# RHR047A_sch3_Processor_5.net
KiCad netlist of a schematic drawn in Altium Designer
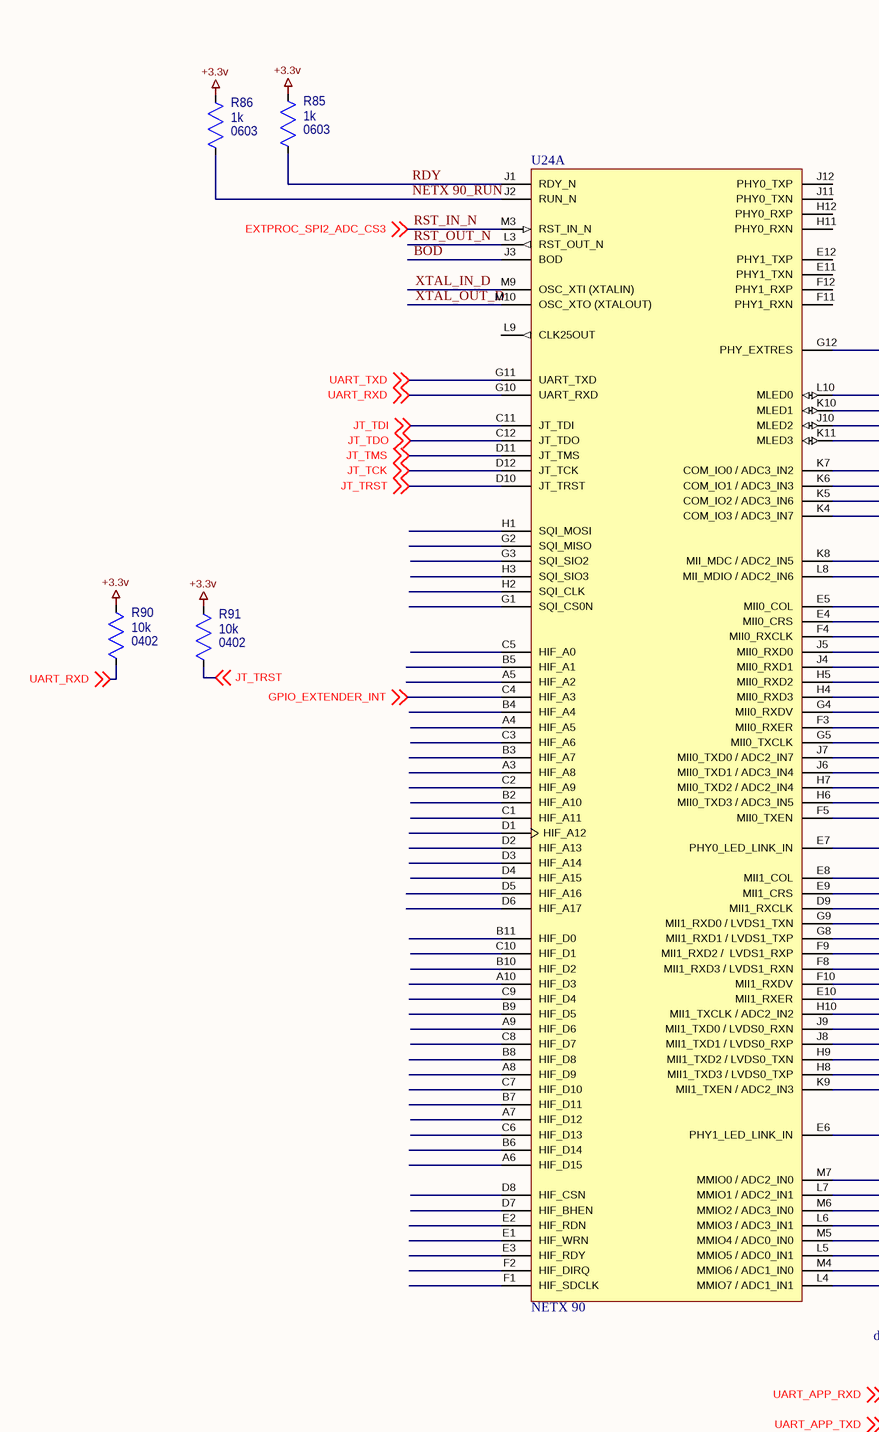
[diagram p0: RHR047A_sch3_Processor_5.SchDoc, left]
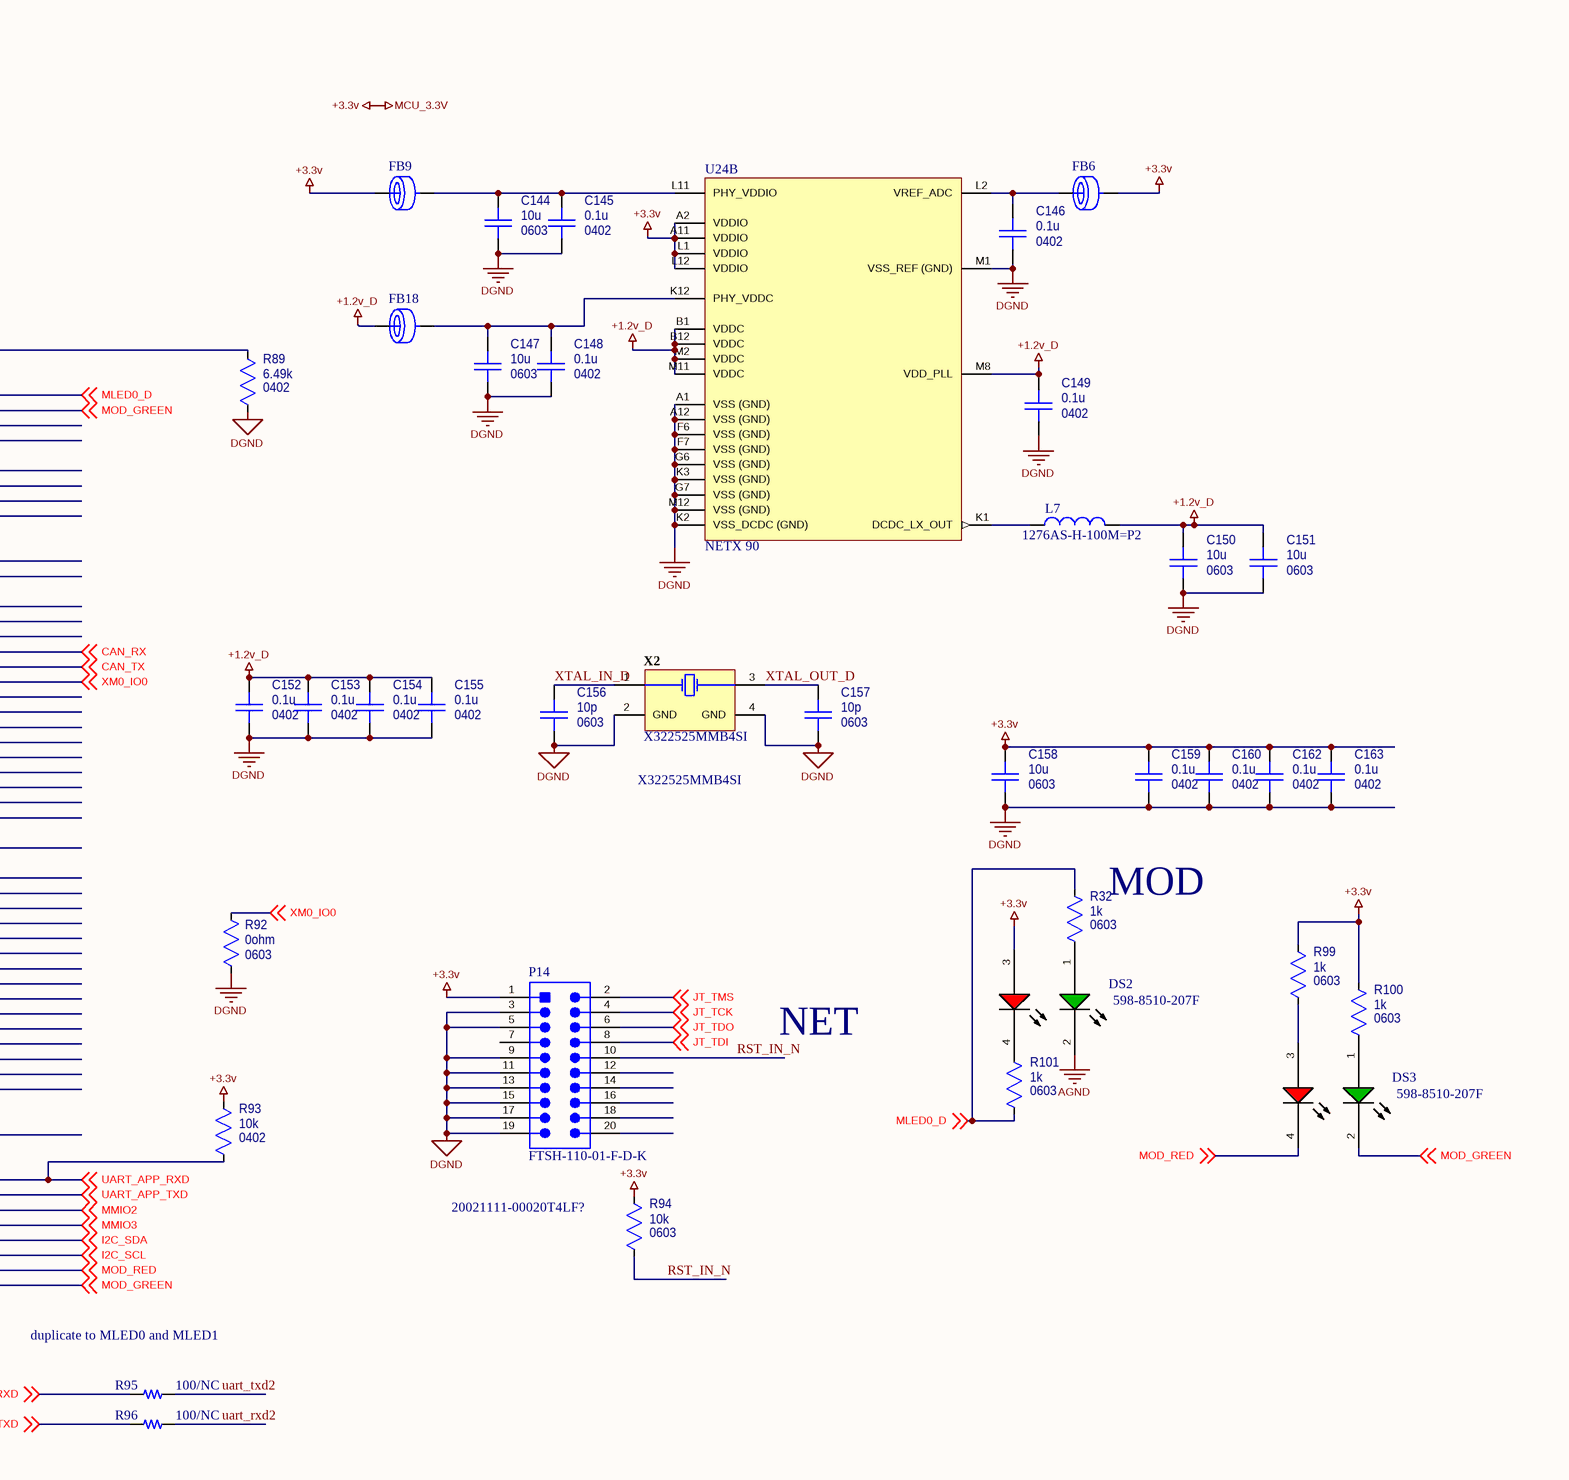
[diagram p1: RHR047A_sch3_Processor_5.SchDoc, right]

(export (version "E")
  (design (tool "Eeschema 10.0.6"))
  (components
    (comp (ref "C144")
      (value "10u")
      (footprint "CAPC1608X092N_0603")
      (description "Capacitor, MLCC")
      (fields
        (field (name "MANUFACTURER") "Murata Electronics")
        (field (name "PARTNUMBER") "GRM188R61A106KE69D")
        (field (name "PACKAGE") "0603")
      )
      (libsource (lib "Karl") (part "Capacitor_0603"))
    )
    (comp (ref "C145")
      (value "0.1u")
      (footprint "CAPC1005X056N_0402")
      (description "Capacitor, MLCC")
      (fields
        (field (name "MANUFACTURER") "Murata Electronics")
        (field (name "PARTNUMBER") "GRM155R71C104KA88J")
        (field (name "PACKAGE") "0402")
      )
      (libsource (lib "Karl") (part "Capacitor_0402"))
    )
    (comp (ref "C146")
      (value "0.1u")
      (footprint "CAPC1005X056N_0402")
      (description "Capacitor, MLCC")
      (fields
        (field (name "MANUFACTURER") "Murata Electronics")
        (field (name "PARTNUMBER") "GRM155R71C104KA88J")
        (field (name "PACKAGE") "0402")
      )
      (libsource (lib "Karl") (part "Capacitor_0402"))
    )
    (comp (ref "C147")
      (value "10u")
      (footprint "CAPC1608X092N_0603")
      (description "Capacitor, MLCC")
      (fields
        (field (name "MANUFACTURER") "Murata Electronics")
        (field (name "PARTNUMBER") "GRM188R61A106KE69D")
        (field (name "PACKAGE") "0603")
      )
      (libsource (lib "Karl") (part "Capacitor_0603"))
    )
    (comp (ref "C148")
      (value "0.1u")
      (footprint "CAPC1005X056N_0402")
      (description "Capacitor, MLCC")
      (fields
        (field (name "MANUFACTURER") "Murata Electronics")
        (field (name "PARTNUMBER") "GRM155R71C104KA88J")
        (field (name "PACKAGE") "0402")
      )
      (libsource (lib "Karl") (part "Capacitor_0402"))
    )
    (comp (ref "C149")
      (value "0.1u")
      (footprint "CAPC1005X056N_0402")
      (description "Capacitor, MLCC")
      (fields
        (field (name "MANUFACTURER") "Murata Electronics")
        (field (name "PARTNUMBER") "GRM155R71C104KA88J")
        (field (name "PACKAGE") "0402")
      )
      (libsource (lib "Karl") (part "Capacitor_0402"))
    )
    (comp (ref "C150")
      (value "10u")
      (footprint "CAPC1608X092N_0603")
      (description "Capacitor, MLCC")
      (fields
        (field (name "MANUFACTURER") "Murata Electronics")
        (field (name "PARTNUMBER") "GRM188R61A106KE69D")
        (field (name "PACKAGE") "0603")
      )
      (libsource (lib "Karl") (part "Capacitor_0603"))
    )
    (comp (ref "C151")
      (value "10u")
      (footprint "CAPC1608X092N_0603")
      (description "Capacitor, MLCC")
      (fields
        (field (name "MANUFACTURER") "Murata Electronics")
        (field (name "PARTNUMBER") "GRM188R61A106KE69D")
        (field (name "PACKAGE") "0603")
      )
      (libsource (lib "Karl") (part "Capacitor_0603"))
    )
    (comp (ref "C152")
      (value "0.1u")
      (footprint "CAPC1005X056N_0402")
      (description "Capacitor, MLCC")
      (fields
        (field (name "MANUFACTURER") "Murata Electronics")
        (field (name "PARTNUMBER") "GRM155R71C104KA88J")
        (field (name "PACKAGE") "0402")
      )
      (libsource (lib "Karl") (part "Capacitor_0402"))
    )
    (comp (ref "C153")
      (value "0.1u")
      (footprint "CAPC1005X056N_0402")
      (description "Capacitor, MLCC")
      (fields
        (field (name "MANUFACTURER") "Murata Electronics")
        (field (name "PARTNUMBER") "GRM155R71C104KA88J")
        (field (name "PACKAGE") "0402")
      )
      (libsource (lib "Karl") (part "Capacitor_0402"))
    )
    (comp (ref "C154")
      (value "0.1u")
      (footprint "CAPC1005X056N_0402")
      (description "Capacitor, MLCC")
      (fields
        (field (name "MANUFACTURER") "Murata Electronics")
        (field (name "PARTNUMBER") "GRM155R71C104KA88J")
        (field (name "PACKAGE") "0402")
      )
      (libsource (lib "Karl") (part "Capacitor_0402"))
    )
    (comp (ref "C155")
      (value "0.1u")
      (footprint "CAPC1005X056N_0402")
      (description "Capacitor, MLCC")
      (fields
        (field (name "MANUFACTURER") "Murata Electronics")
        (field (name "PARTNUMBER") "GRM155R71C104KA88J")
        (field (name "PACKAGE") "0402")
      )
      (libsource (lib "Karl") (part "Capacitor_0402"))
    )
    (comp (ref "C156")
      (value "10p")
      (footprint "CAPC1608X092N_0603")
      (description "Capacitor, MLCC")
      (fields
        (field (name "MANUFACTURER") "Yageo")
        (field (name "PARTNUMBER") "CC0603KRNPO9BN100")
        (field (name "PACKAGE") "0603")
      )
      (libsource (lib "Karl") (part "Capacitor_0603"))
    )
    (comp (ref "C157")
      (value "10p")
      (footprint "CAPC1608X092N_0603")
      (description "Capacitor, MLCC")
      (fields
        (field (name "MANUFACTURER") "Yageo")
        (field (name "PARTNUMBER") "CC0603KRNPO9BN100")
        (field (name "PACKAGE") "0603")
      )
      (libsource (lib "Karl") (part "Capacitor_0603"))
    )
    (comp (ref "C158")
      (value "10u")
      (footprint "CAPC1608X092N_0603")
      (description "Capacitor, MLCC")
      (fields
        (field (name "MANUFACTURER") "Murata Electronics")
        (field (name "PARTNUMBER") "GRM188R61A106KE69D")
        (field (name "PACKAGE") "0603")
      )
      (libsource (lib "Karl") (part "Capacitor_0603"))
    )
    (comp (ref "C159")
      (value "0.1u")
      (footprint "CAPC1005X056N_0402")
      (description "Capacitor, MLCC")
      (fields
        (field (name "MANUFACTURER") "Murata Electronics")
        (field (name "PARTNUMBER") "GRM155R71C104KA88J")
        (field (name "PACKAGE") "0402")
      )
      (libsource (lib "Karl") (part "Capacitor_0402"))
    )
    (comp (ref "C160")
      (value "0.1u")
      (footprint "CAPC1005X056N_0402")
      (description "Capacitor, MLCC")
      (fields
        (field (name "MANUFACTURER") "Murata Electronics")
        (field (name "PARTNUMBER") "GRM155R71C104KA88J")
        (field (name "PACKAGE") "0402")
      )
      (libsource (lib "Karl") (part "Capacitor_0402"))
    )
    (comp (ref "C162")
      (value "0.1u")
      (footprint "CAPC1005X056N_0402")
      (description "Capacitor, MLCC")
      (fields
        (field (name "MANUFACTURER") "Murata Electronics")
        (field (name "PARTNUMBER") "GRM155R71C104KA88J")
        (field (name "PACKAGE") "0402")
      )
      (libsource (lib "Karl") (part "Capacitor_0402"))
    )
    (comp (ref "C163")
      (value "0.1u")
      (footprint "CAPC1005X056N_0402")
      (description "Capacitor, MLCC")
      (fields
        (field (name "MANUFACTURER") "Murata Electronics")
        (field (name "PARTNUMBER") "GRM155R71C104KA88J")
        (field (name "PACKAGE") "0402")
      )
      (libsource (lib "Karl") (part "Capacitor_0402"))
    )
    (comp (ref "DS2")
      (value "598-8510-207F")
      (footprint "DIAL-1208-4_V")
      (description "Bi-Color LED, 2.2 V, -40 to 100 degC, 4-Pin SMD (1208), RoHS, Tape and Reel")
      (fields (field (name "MANUFACTURER") "Dialight"))
      (libsource (lib "Bogen") (part "598-8510-207F"))
    )
    (comp (ref "DS3")
      (value "598-8510-207F")
      (footprint "DIAL-1208-4_V")
      (description "Bi-Color LED, 2.2 V, -40 to 100 degC, 4-Pin SMD (1208), RoHS, Tape and Reel")
      (fields (field (name "MANUFACTURER") "Dialight"))
      (libsource (lib "Bogen") (part "598-8510-207F"))
    )
    (comp (ref "FB6")
      (value "FBC0603")
      (footprint "FBC0603")
      (description "Ferrite Bead Chip")
      (fields
        (field (name "MANUFACTURER") "Pulse Electronics Network")
        (field (name "PARTNUMBER") "PE-0603PFB121ST")
      )
      (libsource (lib "Karl") (part "FBC0603"))
    )
    (comp (ref "FB9")
      (value "FBC0603")
      (footprint "FBC0603")
      (description "Ferrite Bead Chip")
      (fields
        (field (name "MANUFACTURER") "Pulse Electronics Network")
        (field (name "PARTNUMBER") "PE-0603PFB121ST")
      )
      (libsource (lib "Karl") (part "FBC0603"))
    )
    (comp (ref "FB18")
      (value "FBC0603")
      (footprint "FBC0603")
      (description "Ferrite Bead Chip")
      (fields
        (field (name "MANUFACTURER") "Pulse Electronics Network")
        (field (name "PARTNUMBER") "PE-0603PFB121ST")
      )
      (libsource (lib "Karl") (part "FBC0603"))
    )
    (comp (ref "L7")
      (value "1276AS-H-100M=P2")
      (footprint "MURA-IND1210_V")
      (description "Metal alloy Power Inductor, 10 uH, ±20%, 1210 (3225)")
      (fields (field (name "MANUFACTURER") "Murata"))
      (libsource (lib "Bogen") (part "1276AS-H-100M=P2"))
    )
    (comp (ref "P14")
      (value "FTSH-110-01-F-D-K")
      (footprint "SMTC-FTSH-110-01-F-D-K_V")
      (description "Male Header, Pitch 1.27 mm, 2 x 10 Position, Height 6.25 mm, -55 to 125 degC, RoHS")
      (fields (field (name "MANUFACTURER") "Samtec-Inc."))
      (libsource (lib "Bogen") (part "FTSH-110-01-F-D-K"))
    )
    (comp (ref "R32")
      (value "1k")
      (footprint "RESC1608X055N_0603")
      (description "Resistor, Standard")
      (fields
        (field (name "MANUFACTURER") "Yageo")
        (field (name "PARTNUMBER") "RC0603FR-071KL")
        (field (name "PACKAGE") "0603")
      )
      (libsource (lib "Karl") (part "Resistor_0603"))
    )
    (comp (ref "R85")
      (value "1k")
      (footprint "RESC1608X055N_0603")
      (description "Resistor, Standard")
      (fields
        (field (name "MANUFACTURER") "Yageo")
        (field (name "PARTNUMBER") "RC0603FR-071KL")
        (field (name "PACKAGE") "0603")
      )
      (libsource (lib "Karl") (part "Resistor_0603"))
    )
    (comp (ref "R86")
      (value "1k")
      (footprint "RESC1608X055N_0603")
      (description "Resistor, Standard")
      (fields
        (field (name "MANUFACTURER") "Yageo")
        (field (name "PARTNUMBER") "RC0603FR-071KL")
        (field (name "PACKAGE") "0603")
      )
      (libsource (lib "Karl") (part "Resistor_0603"))
    )
    (comp (ref "R89")
      (value "6.49k")
      (footprint "RESC1005X040N_0402")
      (description "Resistor, Standard")
      (fields
        (field (name "MANUFACTURER") "Yageo")
        (field (name "PARTNUMBER") "RC0402FR-076K49L")
        (field (name "PACKAGE") "0402")
      )
      (libsource (lib "Karl") (part "Resistor_0402"))
    )
    (comp (ref "R90")
      (value "10k")
      (footprint "RESC1005X040N_0402")
      (description "Resistor, Standard")
      (fields
        (field (name "MANUFACTURER") "Panasonic")
        (field (name "PARTNUMBER") "ERJ-2RKF1002X")
        (field (name "PACKAGE") "0402")
      )
      (libsource (lib "Karl") (part "Resistor_0402"))
    )
    (comp (ref "R91")
      (value "10k")
      (footprint "RESC1005X040N_0402")
      (description "Resistor, Standard")
      (fields
        (field (name "MANUFACTURER") "Panasonic")
        (field (name "PARTNUMBER") "ERJ-2RKF1002X")
        (field (name "PACKAGE") "0402")
      )
      (libsource (lib "Karl") (part "Resistor_0402"))
    )
    (comp (ref "R92")
      (value "0ohm")
      (footprint "RESC1608X055N_0603")
      (description "Resistor, Standard")
      (fields
        (field (name "MANUFACTURER") "Yageo")
        (field (name "PARTNUMBER") "RC0603JR-070RL")
        (field (name "PACKAGE") "0603")
      )
      (libsource (lib "Karl") (part "Resistor_0603"))
    )
    (comp (ref "R93")
      (value "10k")
      (footprint "RESC1005X040N_0402")
      (description "Resistor, Standard")
      (fields
        (field (name "MANUFACTURER") "Panasonic")
        (field (name "PARTNUMBER") "ERJ-2RKF1002X")
        (field (name "PACKAGE") "0402")
      )
      (libsource (lib "Karl") (part "Resistor_0402"))
    )
    (comp (ref "R94")
      (value "10k")
      (footprint "RESC1608X055N_0603")
      (description "Resistor, Standard")
      (fields
        (field (name "MANUFACTURER") "Yageo")
        (field (name "PARTNUMBER") "RC0603FR-0710KL")
        (field (name "PACKAGE") "0603")
      )
      (libsource (lib "Karl") (part "Resistor_0603"))
    )
    (comp (ref "R95")
      (value "100/NC")
      (footprint "0603R")
      (description "R")
      (libsource (lib "JRJ_1") (part "R"))
    )
    (comp (ref "R96")
      (value "100/NC")
      (footprint "0603R")
      (description "R")
      (libsource (lib "JRJ_1") (part "R"))
    )
    (comp (ref "R99")
      (value "1k")
      (footprint "RESC1608X055N_0603")
      (description "Resistor, Standard")
      (fields
        (field (name "MANUFACTURER") "Yageo")
        (field (name "PARTNUMBER") "RC0603FR-071KL")
        (field (name "PACKAGE") "0603")
      )
      (libsource (lib "Karl") (part "Resistor_0603"))
    )
    (comp (ref "R100")
      (value "1k")
      (footprint "RESC1608X055N_0603")
      (description "Resistor, Standard")
      (fields
        (field (name "MANUFACTURER") "Yageo")
        (field (name "PARTNUMBER") "RC0603FR-071KL")
        (field (name "PACKAGE") "0603")
      )
      (libsource (lib "Karl") (part "Resistor_0603"))
    )
    (comp (ref "R101")
      (value "1k")
      (footprint "RESC1608X055N_0603")
      (description "Resistor, Standard")
      (fields
        (field (name "MANUFACTURER") "Yageo")
        (field (name "PARTNUMBER") "RC0603FR-071KL")
        (field (name "PACKAGE") "0603")
      )
      (libsource (lib "Karl") (part "Resistor_0603"))
    )
    (comp (ref "U24")
      (value "NETX 90")
      (footprint "HILSCH-LFBGA144_V")
      (libsource (lib "Bogen") (part "NETX 90"))
    )
    (comp (ref "X2")
      (value "X322525MMB4SI")
      (footprint "TXC-7M-4_V")
      (description "Seam Crystal, 7M Series, 3 pF, -40 to 85 degC, 4-Pin SMD, RoHS, Tape and Reel")
      (fields (field (name "MANUFACTURER") "TXC"))
      (libsource (lib "Bogen") (part "7M-25.000MEEQ-T"))
    )
  )
  (nets
    (net (code "1") (name "+1.2v_D") (class "Default")
      (node (ref "C149") (pin "1") (pinfunction "1_1") (pintype "passive"))
      (node (ref "C150") (pin "1") (pinfunction "1_1") (pintype "passive"))
      (node (ref "C151") (pin "1") (pinfunction "1_1") (pintype "passive"))
      (node (ref "C152") (pin "1") (pinfunction "1_1") (pintype "passive"))
      (node (ref "C153") (pin "1") (pinfunction "1_1") (pintype "passive"))
      (node (ref "C154") (pin "1") (pinfunction "1_1") (pintype "passive"))
      (node (ref "C155") (pin "1") (pinfunction "1_1") (pintype "passive"))
      (node (ref "FB18") (pin "1") (pinfunction "1_1") (pintype "passive"))
      (node (ref "L7") (pin "2") (pinfunction "2_2") (pintype "passive"))
      (node (ref "U24") (pin "B1") (pinfunction "VDDC_B1") (pintype "power_in"))
      (node (ref "U24") (pin "B12") (pinfunction "VDDC_B12") (pintype "power_in"))
      (node (ref "U24") (pin "M11") (pinfunction "VDDC_M11") (pintype "power_in"))
      (node (ref "U24") (pin "M2") (pinfunction "VDDC_M2") (pintype "power_in"))
      (node (ref "U24") (pin "M8") (pinfunction "VDD_PLL_M8") (pintype "power_in"))
    )
    (net (code "2") (name "+3.3v") (class "Default")
      (node (ref "C158") (pin "1") (pinfunction "1_1") (pintype "passive"))
      (node (ref "C159") (pin "1") (pinfunction "1_1") (pintype "passive"))
      (node (ref "C160") (pin "1") (pinfunction "1_1") (pintype "passive"))
      (node (ref "C162") (pin "1") (pinfunction "1_1") (pintype "passive"))
      (node (ref "C163") (pin "1") (pinfunction "1_1") (pintype "passive"))
      (node (ref "DS2") (pin "3") (pinfunction "RED-A_3") (pintype "passive"))
      (node (ref "FB6") (pin "2") (pinfunction "2_2") (pintype "passive"))
      (node (ref "FB9") (pin "1") (pinfunction "1_1") (pintype "passive"))
      (node (ref "P14") (pin "1") (pinfunction "1_1") (pintype "passive"))
      (node (ref "R100") (pin "2") (pinfunction "2_2") (pintype "passive"))
      (node (ref "R85") (pin "2") (pinfunction "2_2") (pintype "passive"))
      (node (ref "R86") (pin "2") (pinfunction "2_2") (pintype "passive"))
      (node (ref "R90") (pin "2") (pinfunction "2_2") (pintype "passive"))
      (node (ref "R91") (pin "2") (pinfunction "2_2") (pintype "passive"))
      (node (ref "R93") (pin "2") (pinfunction "2_2") (pintype "passive"))
      (node (ref "R94") (pin "2") (pinfunction "2_2") (pintype "passive"))
      (node (ref "R99") (pin "2") (pinfunction "2_2") (pintype "passive"))
      (node (ref "U24") (pin "A11") (pinfunction "VDDIO_A11") (pintype "power_in"))
      (node (ref "U24") (pin "A2") (pinfunction "VDDIO_A2") (pintype "power_in"))
      (node (ref "U24") (pin "L1") (pinfunction "VDDIO_L1") (pintype "power_in"))
      (node (ref "U24") (pin "L12") (pinfunction "VDDIO_L12") (pintype "power_in"))
    )
    (net (code "3") (name "/BOD") (class "Default")
      (node (ref "U24") (pin "J3") (pinfunction "BOD_J3") (pintype "passive"))
    )
    (net (code "4") (name "/NETX 90_RUN") (class "Default")
      (node (ref "R86") (pin "1") (pinfunction "1_1") (pintype "passive"))
      (node (ref "U24") (pin "J2") (pinfunction "RUN_N_J2") (pintype "passive"))
    )
    (net (code "5") (name "/RDY") (class "Default")
      (node (ref "R85") (pin "1") (pinfunction "1_1") (pintype "passive"))
      (node (ref "U24") (pin "J1") (pinfunction "RDY_N_J1") (pintype "passive"))
    )
    (net (code "6") (name "/RST_OUT_N") (class "Default")
      (node (ref "U24") (pin "L3") (pinfunction "RST_OUT_N_L3") (pintype "output"))
    )
    (net (code "7") (name "/XTAL_IN_D") (class "Default")
      (node (ref "C156") (pin "1") (pinfunction "1_1") (pintype "passive"))
      (node (ref "U24") (pin "M9") (pinfunction "OSC_XTI_(XTALIN)_M9") (pintype "passive"))
      (node (ref "X2") (pin "1") (pinfunction "X1_1") (pintype "passive"))
    )
    (net (code "8") (name "/XTAL_OUT_D") (class "Default")
      (node (ref "C157") (pin "1") (pinfunction "1_1") (pintype "passive"))
      (node (ref "U24") (pin "M10") (pinfunction "OSC_XTO_(XTALOUT)_M10") (pintype "passive"))
      (node (ref "X2") (pin "3") (pinfunction "X2_3") (pintype "passive"))
    )
    (net (code "9") (name "/uart_rxd2") (class "Default") (node (ref "R96") (pin "2") (pintype "passive")))
    (net (code "10") (name "/uart_txd2") (class "Default") (node (ref "R95") (pin "2") (pintype "passive")))
    (net (code "11") (name "AGND") (class "Default")
      (node (ref "DS2") (pin "2") (pinfunction "GREEN-K_2") (pintype "passive"))
    )
    (net (code "12") (name "CAN_RX") (class "Default")
      (node (ref "U24") (pin "J5") (pinfunction "MII0_RXD0_J5") (pintype "passive"))
    )
    (net (code "13") (name "CAN_TX") (class "Default")
      (node (ref "U24") (pin "J4") (pinfunction "MII0_RXD1_J4") (pintype "passive"))
    )
    (net (code "14") (name "DGND") (class "Default")
      (node (ref "C144") (pin "2") (pinfunction "2_2") (pintype "passive"))
      (node (ref "C145") (pin "2") (pinfunction "2_2") (pintype "passive"))
      (node (ref "C146") (pin "2") (pinfunction "2_2") (pintype "passive"))
      (node (ref "C147") (pin "2") (pinfunction "2_2") (pintype "passive"))
      (node (ref "C148") (pin "2") (pinfunction "2_2") (pintype "passive"))
      (node (ref "C149") (pin "2") (pinfunction "2_2") (pintype "passive"))
      (node (ref "C150") (pin "2") (pinfunction "2_2") (pintype "passive"))
      (node (ref "C151") (pin "2") (pinfunction "2_2") (pintype "passive"))
      (node (ref "C152") (pin "2") (pinfunction "2_2") (pintype "passive"))
      (node (ref "C153") (pin "2") (pinfunction "2_2") (pintype "passive"))
      (node (ref "C154") (pin "2") (pinfunction "2_2") (pintype "passive"))
      (node (ref "C155") (pin "2") (pinfunction "2_2") (pintype "passive"))
      (node (ref "C156") (pin "2") (pinfunction "2_2") (pintype "passive"))
      (node (ref "C157") (pin "2") (pinfunction "2_2") (pintype "passive"))
      (node (ref "C158") (pin "2") (pinfunction "2_2") (pintype "passive"))
      (node (ref "C159") (pin "2") (pinfunction "2_2") (pintype "passive"))
      (node (ref "C160") (pin "2") (pinfunction "2_2") (pintype "passive"))
      (node (ref "C162") (pin "2") (pinfunction "2_2") (pintype "passive"))
      (node (ref "C163") (pin "2") (pinfunction "2_2") (pintype "passive"))
      (node (ref "P14") (pin "11") (pinfunction "11_11") (pintype "passive"))
      (node (ref "P14") (pin "13") (pinfunction "13_13") (pintype "passive"))
      (node (ref "P14") (pin "15") (pinfunction "15_15") (pintype "passive"))
      (node (ref "P14") (pin "17") (pinfunction "17_17") (pintype "passive"))
      (node (ref "P14") (pin "19") (pinfunction "19_19") (pintype "passive"))
      (node (ref "P14") (pin "3") (pinfunction "3_3") (pintype "passive"))
      (node (ref "P14") (pin "5") (pinfunction "5_5") (pintype "passive"))
      (node (ref "P14") (pin "9") (pinfunction "9_9") (pintype "passive"))
      (node (ref "R89") (pin "1") (pinfunction "1_1") (pintype "passive"))
      (node (ref "R92") (pin "2") (pinfunction "2_2") (pintype "passive"))
      (node (ref "U24") (pin "A1") (pinfunction "VSS_(GND)_A1") (pintype "power_in"))
      (node (ref "U24") (pin "A12") (pinfunction "VSS_(GND)_A12") (pintype "power_in"))
      (node (ref "U24") (pin "F6") (pinfunction "VSS_(GND)_F6") (pintype "power_in"))
      (node (ref "U24") (pin "F7") (pinfunction "VSS_(GND)_F7") (pintype "power_in"))
      (node (ref "U24") (pin "G6") (pinfunction "VSS_(GND)_G6") (pintype "power_in"))
      (node (ref "U24") (pin "G7") (pinfunction "VSS_(GND)_G7") (pintype "power_in"))
      (node (ref "U24") (pin "K2") (pinfunction "VSS_DCDC_(GND)_K2") (pintype "power_in"))
      (node (ref "U24") (pin "K3") (pinfunction "VSS_(GND)_K3") (pintype "power_in"))
      (node (ref "U24") (pin "M1") (pinfunction "VSS_REF_(GND)_M1") (pintype "power_in"))
      (node (ref "U24") (pin "M12") (pinfunction "VSS_(GND)_M12") (pintype "power_in"))
      (node (ref "X2") (pin "2") (pinfunction "GND_2") (pintype "power_in"))
      (node (ref "X2") (pin "4") (pinfunction "GND_4") (pintype "power_in"))
    )
    (net (code "15") (name "EXTPROC_SPI2_ADC_CS3") (class "Default")
      (node (ref "P14") (pin "10") (pinfunction "10_10") (pintype "passive"))
      (node (ref "R94") (pin "1") (pinfunction "1_1") (pintype "passive"))
      (node (ref "U24") (pin "M3") (pinfunction "RST_IN_N_M3") (pintype "input"))
    )
    (net (code "16") (name "GPIO_EXTENDER_INT") (class "Default")
      (node (ref "U24") (pin "C4") (pinfunction "HIF_A3_C4") (pintype "passive"))
    )
    (net (code "17") (name "I2C_SCL") (class "Default")
      (node (ref "U24") (pin "L5") (pinfunction "MMIO5_/_ADC0_IN1_L5") (pintype "passive"))
    )
    (net (code "18") (name "I2C_SDA") (class "Default")
      (node (ref "U24") (pin "M5") (pinfunction "MMIO4_/_ADC0_IN0_M5") (pintype "passive"))
    )
    (net (code "19") (name "JT_TCK") (class "Default")
      (node (ref "P14") (pin "4") (pinfunction "4_4") (pintype "passive"))
      (node (ref "U24") (pin "D12") (pinfunction "JT_TCK_D12") (pintype "passive"))
    )
    (net (code "20") (name "JT_TDI") (class "Default")
      (node (ref "P14") (pin "8") (pinfunction "8_8") (pintype "passive"))
      (node (ref "U24") (pin "C11") (pinfunction "JT_TDI_C11") (pintype "passive"))
    )
    (net (code "21") (name "JT_TDO") (class "Default")
      (node (ref "P14") (pin "6") (pinfunction "6_6") (pintype "passive"))
      (node (ref "U24") (pin "C12") (pinfunction "JT_TDO_C12") (pintype "passive"))
    )
    (net (code "22") (name "JT_TMS") (class "Default")
      (node (ref "P14") (pin "2") (pinfunction "2_2") (pintype "passive"))
      (node (ref "U24") (pin "D11") (pinfunction "JT_TMS_D11") (pintype "passive"))
    )
    (net (code "23") (name "JT_TRST") (class "Default")
      (node (ref "R91") (pin "1") (pinfunction "1_1") (pintype "passive"))
      (node (ref "U24") (pin "D10") (pinfunction "JT_TRST_D10") (pintype "passive"))
    )
    (net (code "24") (name "MLED0_D") (class "Default")
      (node (ref "R101") (pin "1") (pinfunction "1_1") (pintype "passive"))
      (node (ref "R32") (pin "2") (pinfunction "2_2") (pintype "passive"))
      (node (ref "U24") (pin "L10") (pinfunction "MLED0_L10") (pintype "bidirectional"))
    )
    (net (code "25") (name "MMIO2") (class "Default")
      (node (ref "U24") (pin "M6") (pinfunction "MMIO2_/_ADC3_IN0_M6") (pintype "passive"))
    )
    (net (code "26") (name "MMIO3") (class "Default")
      (node (ref "U24") (pin "L6") (pinfunction "MMIO3_/_ADC3_IN1_L6") (pintype "passive"))
    )
    (net (code "27") (name "MOD_GREEN") (class "Default")
      (node (ref "DS3") (pin "2") (pinfunction "GREEN-K_2") (pintype "passive"))
      (node (ref "U24") (pin "K10") (pinfunction "MLED1_K10") (pintype "bidirectional"))
      (node (ref "U24") (pin "L4") (pinfunction "MMIO7_/_ADC1_IN1_L4") (pintype "passive"))
    )
    (net (code "28") (name "MOD_RED") (class "Default")
      (node (ref "DS3") (pin "4") (pinfunction "RED-K_4") (pintype "passive"))
      (node (ref "U24") (pin "M4") (pinfunction "MMIO6_/_ADC1_IN0_M4") (pintype "passive"))
    )
    (net (code "29") (name "Net-(DS2-GREEN-A)") (class "Default")
      (node (ref "DS2") (pin "1") (pinfunction "GREEN-A_1") (pintype "passive"))
      (node (ref "R32") (pin "1") (pinfunction "1_1") (pintype "passive"))
    )
    (net (code "30") (name "Net-(DS2-RED-K)") (class "Default")
      (node (ref "DS2") (pin "4") (pinfunction "RED-K_4") (pintype "passive"))
      (node (ref "R101") (pin "2") (pinfunction "2_2") (pintype "passive"))
    )
    (net (code "31") (name "Net-(DS3-GREEN-A)") (class "Default")
      (node (ref "DS3") (pin "1") (pinfunction "GREEN-A_1") (pintype "passive"))
      (node (ref "R100") (pin "1") (pinfunction "1_1") (pintype "passive"))
    )
    (net (code "32") (name "Net-(DS3-RED-A)") (class "Default")
      (node (ref "DS3") (pin "3") (pinfunction "RED-A_3") (pintype "passive"))
      (node (ref "R99") (pin "1") (pinfunction "1_1") (pintype "passive"))
    )
    (net (code "33") (name "Net-(U24A-PHY_EXTRES)") (class "Default")
      (node (ref "R89") (pin "2") (pinfunction "2_2") (pintype "passive"))
      (node (ref "U24") (pin "G12") (pinfunction "PHY_EXTRES_G12") (pintype "passive"))
    )
    (net (code "34") (name "Net-(U24B-DCDC_LX_OUT)") (class "Default")
      (node (ref "L7") (pin "1") (pinfunction "1_1") (pintype "passive"))
      (node (ref "U24") (pin "K1") (pinfunction "DCDC_LX_OUT_K1") (pintype "output"))
    )
    (net (code "35") (name "Net-(U24B-PHY_VDDC)") (class "Default")
      (node (ref "C147") (pin "1") (pinfunction "1_1") (pintype "passive"))
      (node (ref "C148") (pin "1") (pinfunction "1_1") (pintype "passive"))
      (node (ref "FB18") (pin "2") (pinfunction "2_2") (pintype "passive"))
      (node (ref "U24") (pin "K12") (pinfunction "PHY_VDDC_K12") (pintype "power_in"))
    )
    (net (code "36") (name "Net-(U24B-PHY_VDDIO)") (class "Default")
      (node (ref "C144") (pin "1") (pinfunction "1_1") (pintype "passive"))
      (node (ref "C145") (pin "1") (pinfunction "1_1") (pintype "passive"))
      (node (ref "FB9") (pin "2") (pinfunction "2_2") (pintype "passive"))
      (node (ref "U24") (pin "L11") (pinfunction "PHY_VDDIO_L11") (pintype "power_in"))
    )
    (net (code "37") (name "Net-(U24B-VREF_ADC)") (class "Default")
      (node (ref "C146") (pin "1") (pinfunction "1_1") (pintype "passive"))
      (node (ref "FB6") (pin "1") (pinfunction "1_1") (pintype "passive"))
      (node (ref "U24") (pin "L2") (pinfunction "VREF_ADC_L2") (pintype "power_in"))
    )
    (net (code "38") (name "UART_APP_RXD") (class "Default")
      (node (ref "R93") (pin "1") (pinfunction "1_1") (pintype "passive"))
      (node (ref "R95") (pin "1") (pintype "passive"))
      (node (ref "U24") (pin "M7") (pinfunction "MMIO0_/_ADC2_IN0_M7") (pintype "passive"))
    )
    (net (code "39") (name "UART_APP_TXD") (class "Default")
      (node (ref "R96") (pin "1") (pintype "passive"))
      (node (ref "U24") (pin "L7") (pinfunction "MMIO1_/_ADC2_IN1_L7") (pintype "passive"))
    )
    (net (code "40") (name "UART_RXD") (class "Default")
      (node (ref "R90") (pin "1") (pinfunction "1_1") (pintype "passive"))
      (node (ref "U24") (pin "G10") (pinfunction "UART_RXD_G10") (pintype "passive"))
    )
    (net (code "41") (name "UART_TXD") (class "Default")
      (node (ref "U24") (pin "G11") (pinfunction "UART_TXD_G11") (pintype "passive"))
    )
    (net (code "42") (name "XM0_IO0") (class "Default")
      (node (ref "R92") (pin "1") (pinfunction "1_1") (pintype "passive"))
      (node (ref "U24") (pin "H5") (pinfunction "MII0_RXD2_H5") (pintype "passive"))
    )
    (net (code "43") (name "unconnected-(P14-Pad7)") (class "Default")
      (node (ref "P14") (pin "7") (pinfunction "7_7") (pintype "passive"))
    )
    (net (code "44") (name "unconnected-(P14-Pad12)") (class "Default")
      (node (ref "P14") (pin "12") (pinfunction "12_12") (pintype "passive"))
    )
    (net (code "45") (name "unconnected-(P14-Pad14)") (class "Default")
      (node (ref "P14") (pin "14") (pinfunction "14_14") (pintype "passive"))
    )
    (net (code "46") (name "unconnected-(P14-Pad16)") (class "Default")
      (node (ref "P14") (pin "16") (pinfunction "16_16") (pintype "passive"))
    )
    (net (code "47") (name "unconnected-(P14-Pad18)") (class "Default")
      (node (ref "P14") (pin "18") (pinfunction "18_18") (pintype "passive"))
    )
    (net (code "48") (name "unconnected-(P14-Pad20)") (class "Default")
      (node (ref "P14") (pin "20") (pinfunction "20_20") (pintype "passive"))
    )
    (net (code "49") (name "unconnected-(U24A-CLK25OUT-PadL9)") (class "Default")
      (node (ref "U24") (pin "L9") (pinfunction "CLK25OUT_L9") (pintype "output"))
    )
    (net (code "50") (name "unconnected-(U24A-COM_IO0_{slash}_ADC3_IN2-PadK7)") (class "Default")
      (node (ref "U24") (pin "K7") (pinfunction "COM_IO0_/_ADC3_IN2_K7") (pintype "passive"))
    )
    (net (code "51") (name "unconnected-(U24A-COM_IO1_{slash}_ADC3_IN3-PadK6)") (class "Default")
      (node (ref "U24") (pin "K6") (pinfunction "COM_IO1_/_ADC3_IN3_K6") (pintype "passive"))
    )
    (net (code "52") (name "unconnected-(U24A-COM_IO2_{slash}_ADC3_IN6-PadK5)") (class "Default")
      (node (ref "U24") (pin "K5") (pinfunction "COM_IO2_/_ADC3_IN6_K5") (pintype "passive"))
    )
    (net (code "53") (name "unconnected-(U24A-COM_IO3_{slash}_ADC3_IN7-PadK4)") (class "Default")
      (node (ref "U24") (pin "K4") (pinfunction "COM_IO3_/_ADC3_IN7_K4") (pintype "passive"))
    )
    (net (code "54") (name "unconnected-(U24A-HIF_A0-PadC5)") (class "Default")
      (node (ref "U24") (pin "C5") (pinfunction "HIF_A0_C5") (pintype "passive"))
    )
    (net (code "55") (name "unconnected-(U24A-HIF_A1-PadB5)") (class "Default")
      (node (ref "U24") (pin "B5") (pinfunction "HIF_A1_B5") (pintype "passive"))
    )
    (net (code "56") (name "unconnected-(U24A-HIF_A2-PadA5)") (class "Default")
      (node (ref "U24") (pin "A5") (pinfunction "HIF_A2_A5") (pintype "passive"))
    )
    (net (code "57") (name "unconnected-(U24A-HIF_A4-PadB4)") (class "Default")
      (node (ref "U24") (pin "B4") (pinfunction "HIF_A4_B4") (pintype "passive"))
    )
    (net (code "58") (name "unconnected-(U24A-HIF_A5-PadA4)") (class "Default")
      (node (ref "U24") (pin "A4") (pinfunction "HIF_A5_A4") (pintype "passive"))
    )
    (net (code "59") (name "unconnected-(U24A-HIF_A6-PadC3)") (class "Default")
      (node (ref "U24") (pin "C3") (pinfunction "HIF_A6_C3") (pintype "passive"))
    )
    (net (code "60") (name "unconnected-(U24A-HIF_A7-PadB3)") (class "Default")
      (node (ref "U24") (pin "B3") (pinfunction "HIF_A7_B3") (pintype "passive"))
    )
    (net (code "61") (name "unconnected-(U24A-HIF_A8-PadA3)") (class "Default")
      (node (ref "U24") (pin "A3") (pinfunction "HIF_A8_A3") (pintype "passive"))
    )
    (net (code "62") (name "unconnected-(U24A-HIF_A9-PadC2)") (class "Default")
      (node (ref "U24") (pin "C2") (pinfunction "HIF_A9_C2") (pintype "passive"))
    )
    (net (code "63") (name "unconnected-(U24A-HIF_A10-PadB2)") (class "Default")
      (node (ref "U24") (pin "B2") (pinfunction "HIF_A10_B2") (pintype "passive"))
    )
    (net (code "64") (name "unconnected-(U24A-HIF_A11-PadC1)") (class "Default")
      (node (ref "U24") (pin "C1") (pinfunction "HIF_A11_C1") (pintype "passive"))
    )
    (net (code "65") (name "unconnected-(U24A-HIF_A12-PadD1)") (class "Default")
      (node (ref "U24") (pin "D1") (pinfunction "HIF_A12_D1") (pintype "passive"))
    )
    (net (code "66") (name "unconnected-(U24A-HIF_A13-PadD2)") (class "Default")
      (node (ref "U24") (pin "D2") (pinfunction "HIF_A13_D2") (pintype "passive"))
    )
    (net (code "67") (name "unconnected-(U24A-HIF_A14-PadD3)") (class "Default")
      (node (ref "U24") (pin "D3") (pinfunction "HIF_A14_D3") (pintype "passive"))
    )
    (net (code "68") (name "unconnected-(U24A-HIF_A15-PadD4)") (class "Default")
      (node (ref "U24") (pin "D4") (pinfunction "HIF_A15_D4") (pintype "passive"))
    )
    (net (code "69") (name "unconnected-(U24A-HIF_A16-PadD5)") (class "Default")
      (node (ref "U24") (pin "D5") (pinfunction "HIF_A16_D5") (pintype "passive"))
    )
    (net (code "70") (name "unconnected-(U24A-HIF_A17-PadD6)") (class "Default")
      (node (ref "U24") (pin "D6") (pinfunction "HIF_A17_D6") (pintype "passive"))
    )
    (net (code "71") (name "unconnected-(U24A-HIF_BHEN-PadD7)") (class "Default")
      (node (ref "U24") (pin "D7") (pinfunction "HIF_BHEN_D7") (pintype "passive"))
    )
    (net (code "72") (name "unconnected-(U24A-HIF_CSN-PadD8)") (class "Default")
      (node (ref "U24") (pin "D8") (pinfunction "HIF_CSN_D8") (pintype "passive"))
    )
    (net (code "73") (name "unconnected-(U24A-HIF_D0-PadB11)") (class "Default")
      (node (ref "U24") (pin "B11") (pinfunction "HIF_D0_B11") (pintype "passive"))
    )
    (net (code "74") (name "unconnected-(U24A-HIF_D1-PadC10)") (class "Default")
      (node (ref "U24") (pin "C10") (pinfunction "HIF_D1_C10") (pintype "passive"))
    )
    (net (code "75") (name "unconnected-(U24A-HIF_D2-PadB10)") (class "Default")
      (node (ref "U24") (pin "B10") (pinfunction "HIF_D2_B10") (pintype "passive"))
    )
    (net (code "76") (name "unconnected-(U24A-HIF_D3-PadA10)") (class "Default")
      (node (ref "U24") (pin "A10") (pinfunction "HIF_D3_A10") (pintype "passive"))
    )
    (net (code "77") (name "unconnected-(U24A-HIF_D4-PadC9)") (class "Default")
      (node (ref "U24") (pin "C9") (pinfunction "HIF_D4_C9") (pintype "passive"))
    )
    (net (code "78") (name "unconnected-(U24A-HIF_D5-PadB9)") (class "Default")
      (node (ref "U24") (pin "B9") (pinfunction "HIF_D5_B9") (pintype "passive"))
    )
    (net (code "79") (name "unconnected-(U24A-HIF_D6-PadA9)") (class "Default")
      (node (ref "U24") (pin "A9") (pinfunction "HIF_D6_A9") (pintype "passive"))
    )
    (net (code "80") (name "unconnected-(U24A-HIF_D7-PadC8)") (class "Default")
      (node (ref "U24") (pin "C8") (pinfunction "HIF_D7_C8") (pintype "passive"))
    )
    (net (code "81") (name "unconnected-(U24A-HIF_D8-PadB8)") (class "Default")
      (node (ref "U24") (pin "B8") (pinfunction "HIF_D8_B8") (pintype "passive"))
    )
    (net (code "82") (name "unconnected-(U24A-HIF_D9-PadA8)") (class "Default")
      (node (ref "U24") (pin "A8") (pinfunction "HIF_D9_A8") (pintype "passive"))
    )
    (net (code "83") (name "unconnected-(U24A-HIF_D10-PadC7)") (class "Default")
      (node (ref "U24") (pin "C7") (pinfunction "HIF_D10_C7") (pintype "passive"))
    )
    (net (code "84") (name "unconnected-(U24A-HIF_D11-PadB7)") (class "Default")
      (node (ref "U24") (pin "B7") (pinfunction "HIF_D11_B7") (pintype "passive"))
    )
    (net (code "85") (name "unconnected-(U24A-HIF_D12-PadA7)") (class "Default")
      (node (ref "U24") (pin "A7") (pinfunction "HIF_D12_A7") (pintype "passive"))
    )
    (net (code "86") (name "unconnected-(U24A-HIF_D13-PadC6)") (class "Default")
      (node (ref "U24") (pin "C6") (pinfunction "HIF_D13_C6") (pintype "passive"))
    )
    (net (code "87") (name "unconnected-(U24A-HIF_D14-PadB6)") (class "Default")
      (node (ref "U24") (pin "B6") (pinfunction "HIF_D14_B6") (pintype "passive"))
    )
    (net (code "88") (name "unconnected-(U24A-HIF_D15-PadA6)") (class "Default")
      (node (ref "U24") (pin "A6") (pinfunction "HIF_D15_A6") (pintype "passive"))
    )
    (net (code "89") (name "unconnected-(U24A-HIF_DIRQ-PadF2)") (class "Default")
      (node (ref "U24") (pin "F2") (pinfunction "HIF_DIRQ_F2") (pintype "passive"))
    )
    (net (code "90") (name "unconnected-(U24A-HIF_RDN-PadE2)") (class "Default")
      (node (ref "U24") (pin "E2") (pinfunction "HIF_RDN_E2") (pintype "passive"))
    )
    (net (code "91") (name "unconnected-(U24A-HIF_RDY-PadE3)") (class "Default")
      (node (ref "U24") (pin "E3") (pinfunction "HIF_RDY_E3") (pintype "passive"))
    )
    (net (code "92") (name "unconnected-(U24A-HIF_SDCLK-PadF1)") (class "Default")
      (node (ref "U24") (pin "F1") (pinfunction "HIF_SDCLK_F1") (pintype "passive"))
    )
    (net (code "93") (name "unconnected-(U24A-HIF_WRN-PadE1)") (class "Default")
      (node (ref "U24") (pin "E1") (pinfunction "HIF_WRN_E1") (pintype "passive"))
    )
    (net (code "94") (name "unconnected-(U24A-MII0_COL-PadE5)") (class "Default")
      (node (ref "U24") (pin "E5") (pinfunction "MII0_COL_E5") (pintype "passive"))
    )
    (net (code "95") (name "unconnected-(U24A-MII0_CRS-PadE4)") (class "Default")
      (node (ref "U24") (pin "E4") (pinfunction "MII0_CRS_E4") (pintype "passive"))
    )
    (net (code "96") (name "unconnected-(U24A-MII0_RXCLK-PadF4)") (class "Default")
      (node (ref "U24") (pin "F4") (pinfunction "MII0_RXCLK_F4") (pintype "passive"))
    )
    (net (code "97") (name "unconnected-(U24A-MII0_RXD3-PadH4)") (class "Default")
      (node (ref "U24") (pin "H4") (pinfunction "MII0_RXD3_H4") (pintype "passive"))
    )
    (net (code "98") (name "unconnected-(U24A-MII0_RXDV-PadG4)") (class "Default")
      (node (ref "U24") (pin "G4") (pinfunction "MII0_RXDV_G4") (pintype "passive"))
    )
    (net (code "99") (name "unconnected-(U24A-MII0_RXER-PadF3)") (class "Default")
      (node (ref "U24") (pin "F3") (pinfunction "MII0_RXER_F3") (pintype "passive"))
    )
    (net (code "100") (name "unconnected-(U24A-MII0_TXCLK-PadG5)") (class "Default")
      (node (ref "U24") (pin "G5") (pinfunction "MII0_TXCLK_G5") (pintype "passive"))
    )
    (net (code "101") (name "unconnected-(U24A-MII0_TXD0_{slash}_ADC2_IN7-PadJ7)") (class "Default")
      (node (ref "U24") (pin "J7") (pinfunction "MII0_TXD0_/_ADC2_IN7_J7") (pintype "passive"))
    )
    (net (code "102") (name "unconnected-(U24A-MII0_TXD1_{slash}_ADC3_IN4-PadJ6)") (class "Default")
      (node (ref "U24") (pin "J6") (pinfunction "MII0_TXD1_/_ADC3_IN4_J6") (pintype "passive"))
    )
    (net (code "103") (name "unconnected-(U24A-MII0_TXD2_{slash}_ADC2_IN4-PadH7)") (class "Default")
      (node (ref "U24") (pin "H7") (pinfunction "MII0_TXD2_/_ADC2_IN4_H7") (pintype "passive"))
    )
    (net (code "104") (name "unconnected-(U24A-MII0_TXD3_{slash}_ADC3_IN5-PadH6)") (class "Default")
      (node (ref "U24") (pin "H6") (pinfunction "MII0_TXD3_/_ADC3_IN5_H6") (pintype "passive"))
    )
    (net (code "105") (name "unconnected-(U24A-MII0_TXEN-PadF5)") (class "Default")
      (node (ref "U24") (pin "F5") (pinfunction "MII0_TXEN_F5") (pintype "passive"))
    )
    (net (code "106") (name "unconnected-(U24A-MII1_COL-PadE8)") (class "Default")
      (node (ref "U24") (pin "E8") (pinfunction "MII1_COL_E8") (pintype "passive"))
    )
    (net (code "107") (name "unconnected-(U24A-MII1_CRS-PadE9)") (class "Default")
      (node (ref "U24") (pin "E9") (pinfunction "MII1_CRS_E9") (pintype "passive"))
    )
    (net (code "108") (name "unconnected-(U24A-MII1_RXCLK-PadD9)") (class "Default")
      (node (ref "U24") (pin "D9") (pinfunction "MII1_RXCLK_D9") (pintype "passive"))
    )
    (net (code "109") (name "unconnected-(U24A-MII1_RXD0_{slash}_LVDS1_TXN-PadG9)") (class "Default")
      (node (ref "U24") (pin "G9") (pinfunction "MII1_RXD0_/_LVDS1_TXN_G9") (pintype "passive"))
    )
    (net (code "110") (name "unconnected-(U24A-MII1_RXD1_{slash}_LVDS1_TXP-PadG8)") (class "Default")
      (node (ref "U24") (pin "G8") (pinfunction "MII1_RXD1_/_LVDS1_TXP_G8") (pintype "passive"))
    )
    (net (code "111") (name "unconnected-(U24A-MII1_RXD2_{slash}__LVDS1_RXP-PadF9)") (class "Default")
      (node (ref "U24") (pin "F9") (pinfunction "MII1_RXD2_/__LVDS1_RXP_F9") (pintype "passive"))
    )
    (net (code "112") (name "unconnected-(U24A-MII1_RXD3_{slash}_LVDS1_RXN-PadF8)") (class "Default")
      (node (ref "U24") (pin "F8") (pinfunction "MII1_RXD3_/_LVDS1_RXN_F8") (pintype "passive"))
    )
    (net (code "113") (name "unconnected-(U24A-MII1_RXDV-PadF10)") (class "Default")
      (node (ref "U24") (pin "F10") (pinfunction "MII1_RXDV_F10") (pintype "passive"))
    )
    (net (code "114") (name "unconnected-(U24A-MII1_RXER-PadE10)") (class "Default")
      (node (ref "U24") (pin "E10") (pinfunction "MII1_RXER_E10") (pintype "passive"))
    )
    (net (code "115") (name "unconnected-(U24A-MII1_TXCLK_{slash}_ADC2_IN2-PadH10)") (class "Default")
      (node (ref "U24") (pin "H10") (pinfunction "MII1_TXCLK_/_ADC2_IN2_H10") (pintype "passive"))
    )
    (net (code "116") (name "unconnected-(U24A-MII1_TXD0_{slash}_LVDS0_RXN-PadJ9)") (class "Default")
      (node (ref "U24") (pin "J9") (pinfunction "MII1_TXD0_/_LVDS0_RXN_J9") (pintype "passive"))
    )
    (net (code "117") (name "unconnected-(U24A-MII1_TXD1_{slash}_LVDS0_RXP-PadJ8)") (class "Default")
      (node (ref "U24") (pin "J8") (pinfunction "MII1_TXD1_/_LVDS0_RXP_J8") (pintype "passive"))
    )
    (net (code "118") (name "unconnected-(U24A-MII1_TXD2_{slash}_LVDS0_TXN-PadH9)") (class "Default")
      (node (ref "U24") (pin "H9") (pinfunction "MII1_TXD2_/_LVDS0_TXN_H9") (pintype "passive"))
    )
    (net (code "119") (name "unconnected-(U24A-MII1_TXD3_{slash}_LVDS0_TXP-PadH8)") (class "Default")
      (node (ref "U24") (pin "H8") (pinfunction "MII1_TXD3_/_LVDS0_TXP_H8") (pintype "passive"))
    )
    (net (code "120") (name "unconnected-(U24A-MII1_TXEN_{slash}_ADC2_IN3-PadK9)") (class "Default")
      (node (ref "U24") (pin "K9") (pinfunction "MII1_TXEN_/_ADC2_IN3_K9") (pintype "passive"))
    )
    (net (code "121") (name "unconnected-(U24A-MII_MDC_{slash}_ADC2_IN5-PadK8)") (class "Default")
      (node (ref "U24") (pin "K8") (pinfunction "MII_MDC_/_ADC2_IN5_K8") (pintype "passive"))
    )
    (net (code "122") (name "unconnected-(U24A-MII_MDIO_{slash}_ADC2_IN6-PadL8)") (class "Default")
      (node (ref "U24") (pin "L8") (pinfunction "MII_MDIO_/_ADC2_IN6_L8") (pintype "passive"))
    )
    (net (code "123") (name "unconnected-(U24A-MLED2-PadJ10)") (class "Default")
      (node (ref "U24") (pin "J10") (pinfunction "MLED2_J10") (pintype "bidirectional"))
    )
    (net (code "124") (name "unconnected-(U24A-MLED3-PadK11)") (class "Default")
      (node (ref "U24") (pin "K11") (pinfunction "MLED3_K11") (pintype "bidirectional"))
    )
    (net (code "125") (name "unconnected-(U24A-PHY0_LED_LINK_IN-PadE7)") (class "Default")
      (node (ref "U24") (pin "E7") (pinfunction "PHY0_LED_LINK_IN_E7") (pintype "passive"))
    )
    (net (code "126") (name "unconnected-(U24A-PHY0_RXN-PadH11)") (class "Default")
      (node (ref "U24") (pin "H11") (pinfunction "PHY0_RXN_H11") (pintype "passive"))
    )
    (net (code "127") (name "unconnected-(U24A-PHY0_RXP-PadH12)") (class "Default")
      (node (ref "U24") (pin "H12") (pinfunction "PHY0_RXP_H12") (pintype "passive"))
    )
    (net (code "128") (name "unconnected-(U24A-PHY0_TXN-PadJ11)") (class "Default")
      (node (ref "U24") (pin "J11") (pinfunction "PHY0_TXN_J11") (pintype "passive"))
    )
    (net (code "129") (name "unconnected-(U24A-PHY0_TXP-PadJ12)") (class "Default")
      (node (ref "U24") (pin "J12") (pinfunction "PHY0_TXP_J12") (pintype "passive"))
    )
    (net (code "130") (name "unconnected-(U24A-PHY1_LED_LINK_IN-PadE6)") (class "Default")
      (node (ref "U24") (pin "E6") (pinfunction "PHY1_LED_LINK_IN_E6") (pintype "passive"))
    )
    (net (code "131") (name "unconnected-(U24A-PHY1_RXN-PadF11)") (class "Default")
      (node (ref "U24") (pin "F11") (pinfunction "PHY1_RXN_F11") (pintype "passive"))
    )
    (net (code "132") (name "unconnected-(U24A-PHY1_RXP-PadF12)") (class "Default")
      (node (ref "U24") (pin "F12") (pinfunction "PHY1_RXP_F12") (pintype "passive"))
    )
    (net (code "133") (name "unconnected-(U24A-PHY1_TXN-PadE11)") (class "Default")
      (node (ref "U24") (pin "E11") (pinfunction "PHY1_TXN_E11") (pintype "passive"))
    )
    (net (code "134") (name "unconnected-(U24A-PHY1_TXP-PadE12)") (class "Default")
      (node (ref "U24") (pin "E12") (pinfunction "PHY1_TXP_E12") (pintype "passive"))
    )
    (net (code "135") (name "unconnected-(U24A-SQI_CLK-PadH2)") (class "Default")
      (node (ref "U24") (pin "H2") (pinfunction "SQI_CLK_H2") (pintype "passive"))
    )
    (net (code "136") (name "unconnected-(U24A-SQI_CS0N-PadG1)") (class "Default")
      (node (ref "U24") (pin "G1") (pinfunction "SQI_CS0N_G1") (pintype "passive"))
    )
    (net (code "137") (name "unconnected-(U24A-SQI_MISO-PadG2)") (class "Default")
      (node (ref "U24") (pin "G2") (pinfunction "SQI_MISO_G2") (pintype "passive"))
    )
    (net (code "138") (name "unconnected-(U24A-SQI_MOSI-PadH1)") (class "Default")
      (node (ref "U24") (pin "H1") (pinfunction "SQI_MOSI_H1") (pintype "passive"))
    )
    (net (code "139") (name "unconnected-(U24A-SQI_SIO2-PadG3)") (class "Default")
      (node (ref "U24") (pin "G3") (pinfunction "SQI_SIO2_G3") (pintype "passive"))
    )
    (net (code "140") (name "unconnected-(U24A-SQI_SIO3-PadH3)") (class "Default")
      (node (ref "U24") (pin "H3") (pinfunction "SQI_SIO3_H3") (pintype "passive"))
    )
  )
)
